# BIOMatrix.net
KiCad netlist of a schematic drawn in EAGLE
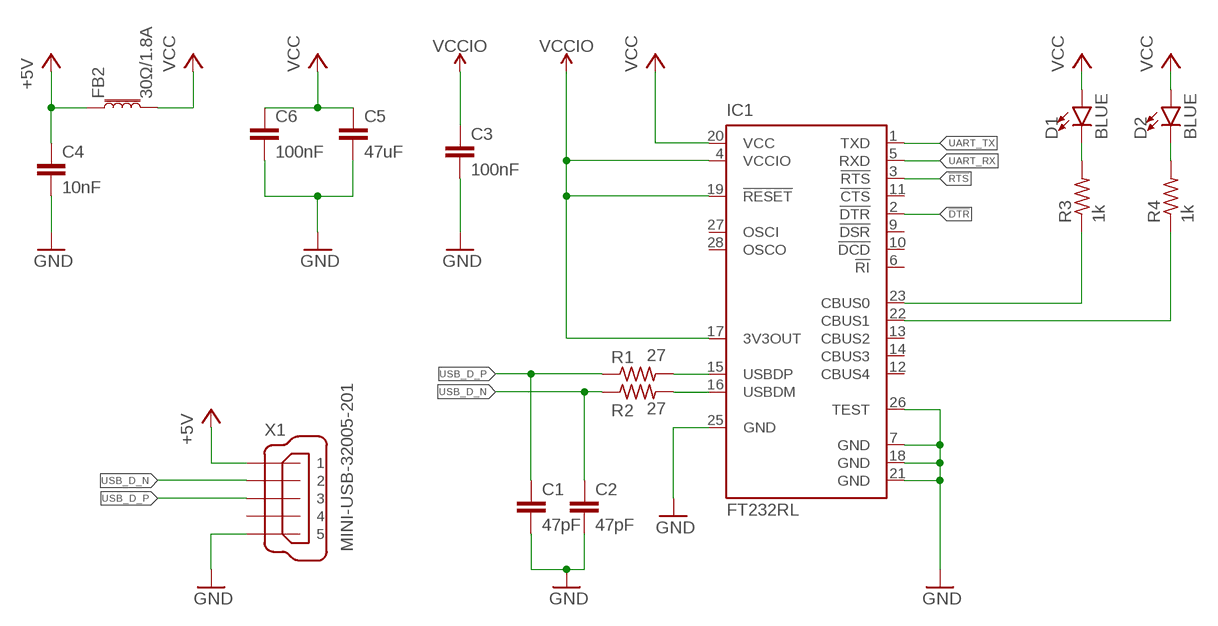
[diagram p0: schematic, sheet 1]

(export (version "E")
  (design (tool "Eeschema 10.0.6"))
  (components
    (comp (ref "C1")
      (value "47pF")
      (footprint "eagle-import:C0603")
      (libsource (lib "eagle-import") (part "C-EUC0603"))
    )
    (comp (ref "C2")
      (value "47pF")
      (footprint "eagle-import:C0603")
      (libsource (lib "eagle-import") (part "C-EUC0603"))
    )
    (comp (ref "C3")
      (value "100nF")
      (footprint "eagle-import:C0603")
      (libsource (lib "eagle-import") (part "C-EUC0603"))
    )
    (comp (ref "C4")
      (value "10nF")
      (footprint "eagle-import:C0603")
      (libsource (lib "eagle-import") (part "C-EUC0603"))
    )
    (comp (ref "C5")
      (value "47uF")
      (footprint "eagle-import:C0603")
      (libsource (lib "eagle-import") (part "C-EUC0603"))
    )
    (comp (ref "C6")
      (value "100nF")
      (footprint "eagle-import:C0603")
      (libsource (lib "eagle-import") (part "C-EUC0603"))
    )
    (comp (ref "D1")
      (value "BLUE")
      (footprint "eagle-import:LED-0603")
      (libsource (lib "eagle-import") (part "LED-BLUE0603"))
    )
    (comp (ref "D2")
      (value "BLUE")
      (footprint "eagle-import:LED-0603")
      (libsource (lib "eagle-import") (part "LED-BLUE0603"))
    )
    (comp (ref "FB2")
      (value "30Ω/1.8A")
      (footprint "eagle-import:0603")
      (libsource (lib "eagle-import") (part "FERRITE_BEAD-0603"))
    )
    (comp (ref "IC1")
      (value "FT232RL")
      (footprint "eagle-import:SSOP28")
      (libsource (lib "eagle-import") (part "FT232RL"))
    )
    (comp (ref "R1")
      (value "27")
      (footprint "eagle-import:R0603")
      (libsource (lib "eagle-import") (part "R-US_R0603"))
    )
    (comp (ref "R2")
      (value "27")
      (footprint "eagle-import:R0603")
      (libsource (lib "eagle-import") (part "R-US_R0603"))
    )
    (comp (ref "R3")
      (value "1k")
      (footprint "eagle-import:R0603")
      (libsource (lib "eagle-import") (part "R-US_R0603"))
    )
    (comp (ref "R4")
      (value "1k")
      (footprint "eagle-import:R0603")
      (libsource (lib "eagle-import") (part "R-US_R0603"))
    )
    (comp (ref "X1")
      (value "MINI-USB-32005-201")
      (footprint "eagle-import:32005-201")
      (libsource (lib "eagle-import") (part "MINI-USB-32005-201"))
    )
  )
  (nets
    (net (code "1") (name "+5V") (class "Default")
      (node (ref "C4") (pin "1") (pinfunction "1_1") (pintype "passive"))
      (node (ref "FB2") (pin "1") (pinfunction "1_1") (pintype "passive"))
      (node (ref "X1") (pin "1") (pinfunction "1_1") (pintype "passive"))
    )
    (net (code "2") (name "/~{DTR}") (class "Default")
      (node (ref "IC1") (pin "2") (pinfunction "~{DTR}_2") (pintype "output"))
    )
    (net (code "3") (name "/~{RTS}") (class "Default")
      (node (ref "IC1") (pin "3") (pinfunction "~{RTS}_3") (pintype "output"))
    )
    (net (code "4") (name "GND") (class "Default")
      (node (ref "C1") (pin "2") (pinfunction "2_2") (pintype "passive"))
      (node (ref "C2") (pin "2") (pinfunction "2_2") (pintype "passive"))
      (node (ref "C3") (pin "2") (pinfunction "2_2") (pintype "passive"))
      (node (ref "C4") (pin "2") (pinfunction "2_2") (pintype "passive"))
      (node (ref "C5") (pin "2") (pinfunction "2_2") (pintype "passive"))
      (node (ref "C6") (pin "2") (pinfunction "2_2") (pintype "passive"))
      (node (ref "IC1") (pin "18") (pinfunction "GND_18") (pintype "power_in"))
      (node (ref "IC1") (pin "21") (pinfunction "GND_21") (pintype "power_in"))
      (node (ref "IC1") (pin "25") (pinfunction "GND_25") (pintype "power_in"))
      (node (ref "IC1") (pin "26") (pinfunction "TEST_26") (pintype "input"))
      (node (ref "IC1") (pin "7") (pinfunction "GND_7") (pintype "power_in"))
      (node (ref "X1") (pin "5") (pinfunction "5_5") (pintype "passive"))
    )
    (net (code "5") (name "Net-(D1-PadC)") (class "Default")
      (node (ref "D1") (pin "C") (pinfunction "C_C") (pintype "passive"))
      (node (ref "R3") (pin "2") (pinfunction "2_2") (pintype "passive"))
    )
    (net (code "6") (name "Net-(D2-PadC)") (class "Default")
      (node (ref "D2") (pin "C") (pinfunction "C_C") (pintype "passive"))
      (node (ref "R4") (pin "2") (pinfunction "2_2") (pintype "passive"))
    )
    (net (code "7") (name "Net-(IC1-CBUS0)") (class "Default")
      (node (ref "IC1") (pin "23") (pinfunction "CBUS0_23") (pintype "bidirectional"))
      (node (ref "R3") (pin "1") (pinfunction "1_1") (pintype "passive"))
    )
    (net (code "8") (name "Net-(IC1-CBUS1)") (class "Default")
      (node (ref "IC1") (pin "22") (pinfunction "CBUS1_22") (pintype "bidirectional"))
      (node (ref "R4") (pin "1") (pinfunction "1_1") (pintype "passive"))
    )
    (net (code "9") (name "Net-(IC1-USBDM)") (class "Default")
      (node (ref "IC1") (pin "16") (pinfunction "USBDM_16") (pintype "bidirectional"))
      (node (ref "R2") (pin "2") (pinfunction "2_2") (pintype "passive"))
    )
    (net (code "10") (name "Net-(IC1-USBDP)") (class "Default")
      (node (ref "IC1") (pin "15") (pinfunction "USBDP_15") (pintype "bidirectional"))
      (node (ref "R1") (pin "2") (pinfunction "2_2") (pintype "passive"))
    )
    (net (code "11") (name "UART_RX") (class "Default")
      (node (ref "IC1") (pin "5") (pinfunction "RXD_5") (pintype "input"))
    )
    (net (code "12") (name "UART_TX") (class "Default")
      (node (ref "IC1") (pin "1") (pinfunction "TXD_1") (pintype "output"))
    )
    (net (code "13") (name "USB_D_N") (class "Default")
      (node (ref "C2") (pin "1") (pinfunction "1_1") (pintype "passive"))
      (node (ref "R2") (pin "1") (pinfunction "1_1") (pintype "passive"))
      (node (ref "X1") (pin "2") (pinfunction "2_2") (pintype "passive"))
    )
    (net (code "14") (name "USB_D_P") (class "Default")
      (node (ref "C1") (pin "1") (pinfunction "1_1") (pintype "passive"))
      (node (ref "R1") (pin "1") (pinfunction "1_1") (pintype "passive"))
      (node (ref "X1") (pin "3") (pinfunction "3_3") (pintype "passive"))
    )
    (net (code "15") (name "VCC") (class "Default")
      (node (ref "C5") (pin "1") (pinfunction "1_1") (pintype "passive"))
      (node (ref "C6") (pin "1") (pinfunction "1_1") (pintype "passive"))
      (node (ref "D1") (pin "A") (pinfunction "A_A") (pintype "passive"))
      (node (ref "D2") (pin "A") (pinfunction "A_A") (pintype "passive"))
      (node (ref "FB2") (pin "2") (pinfunction "2_2") (pintype "passive"))
      (node (ref "IC1") (pin "20") (pinfunction "VCC_20") (pintype "power_in"))
    )
    (net (code "16") (name "VCCIO") (class "Default")
      (node (ref "C3") (pin "1") (pinfunction "1_1") (pintype "passive"))
      (node (ref "IC1") (pin "17") (pinfunction "3V3OUT_17") (pintype "output"))
      (node (ref "IC1") (pin "19") (pinfunction "~{RESET}_19") (pintype "input"))
      (node (ref "IC1") (pin "4") (pinfunction "VCCIO_4") (pintype "power_in"))
    )
    (net (code "17") (name "unconnected-(IC1-CBUS2-Pad13)") (class "Default")
      (node (ref "IC1") (pin "13") (pinfunction "CBUS2_13") (pintype "bidirectional"))
    )
    (net (code "18") (name "unconnected-(IC1-CBUS3-Pad14)") (class "Default")
      (node (ref "IC1") (pin "14") (pinfunction "CBUS3_14") (pintype "bidirectional"))
    )
    (net (code "19") (name "unconnected-(IC1-CBUS4-Pad12)") (class "Default")
      (node (ref "IC1") (pin "12") (pinfunction "CBUS4_12") (pintype "bidirectional"))
    )
    (net (code "20") (name "unconnected-(IC1-OSCI-Pad27)") (class "Default")
      (node (ref "IC1") (pin "27") (pinfunction "OSCI_27") (pintype "input"))
    )
    (net (code "21") (name "unconnected-(IC1-OSCO-Pad28)") (class "Default")
      (node (ref "IC1") (pin "28") (pinfunction "OSCO_28") (pintype "output"))
    )
    (net (code "22") (name "unconnected-(IC1-~{CTS}-Pad11)") (class "Default")
      (node (ref "IC1") (pin "11") (pinfunction "~{CTS}_11") (pintype "input"))
    )
    (net (code "23") (name "unconnected-(IC1-~{DCD}-Pad10)") (class "Default")
      (node (ref "IC1") (pin "10") (pinfunction "~{DCD}_10") (pintype "input"))
    )
    (net (code "24") (name "unconnected-(IC1-~{DSR}-Pad9)") (class "Default")
      (node (ref "IC1") (pin "9") (pinfunction "~{DSR}_9") (pintype "input"))
    )
    (net (code "25") (name "unconnected-(IC1-~{RI}-Pad6)") (class "Default")
      (node (ref "IC1") (pin "6") (pinfunction "~{RI}_6") (pintype "input"))
    )
    (net (code "26") (name "unconnected-(X1-Pad4)") (class "Default")
      (node (ref "X1") (pin "4") (pinfunction "4_4") (pintype "passive"))
    )
  )
)
